# Motor-BLDC.net
KiCad netlist of a schematic drawn in Altium Designer
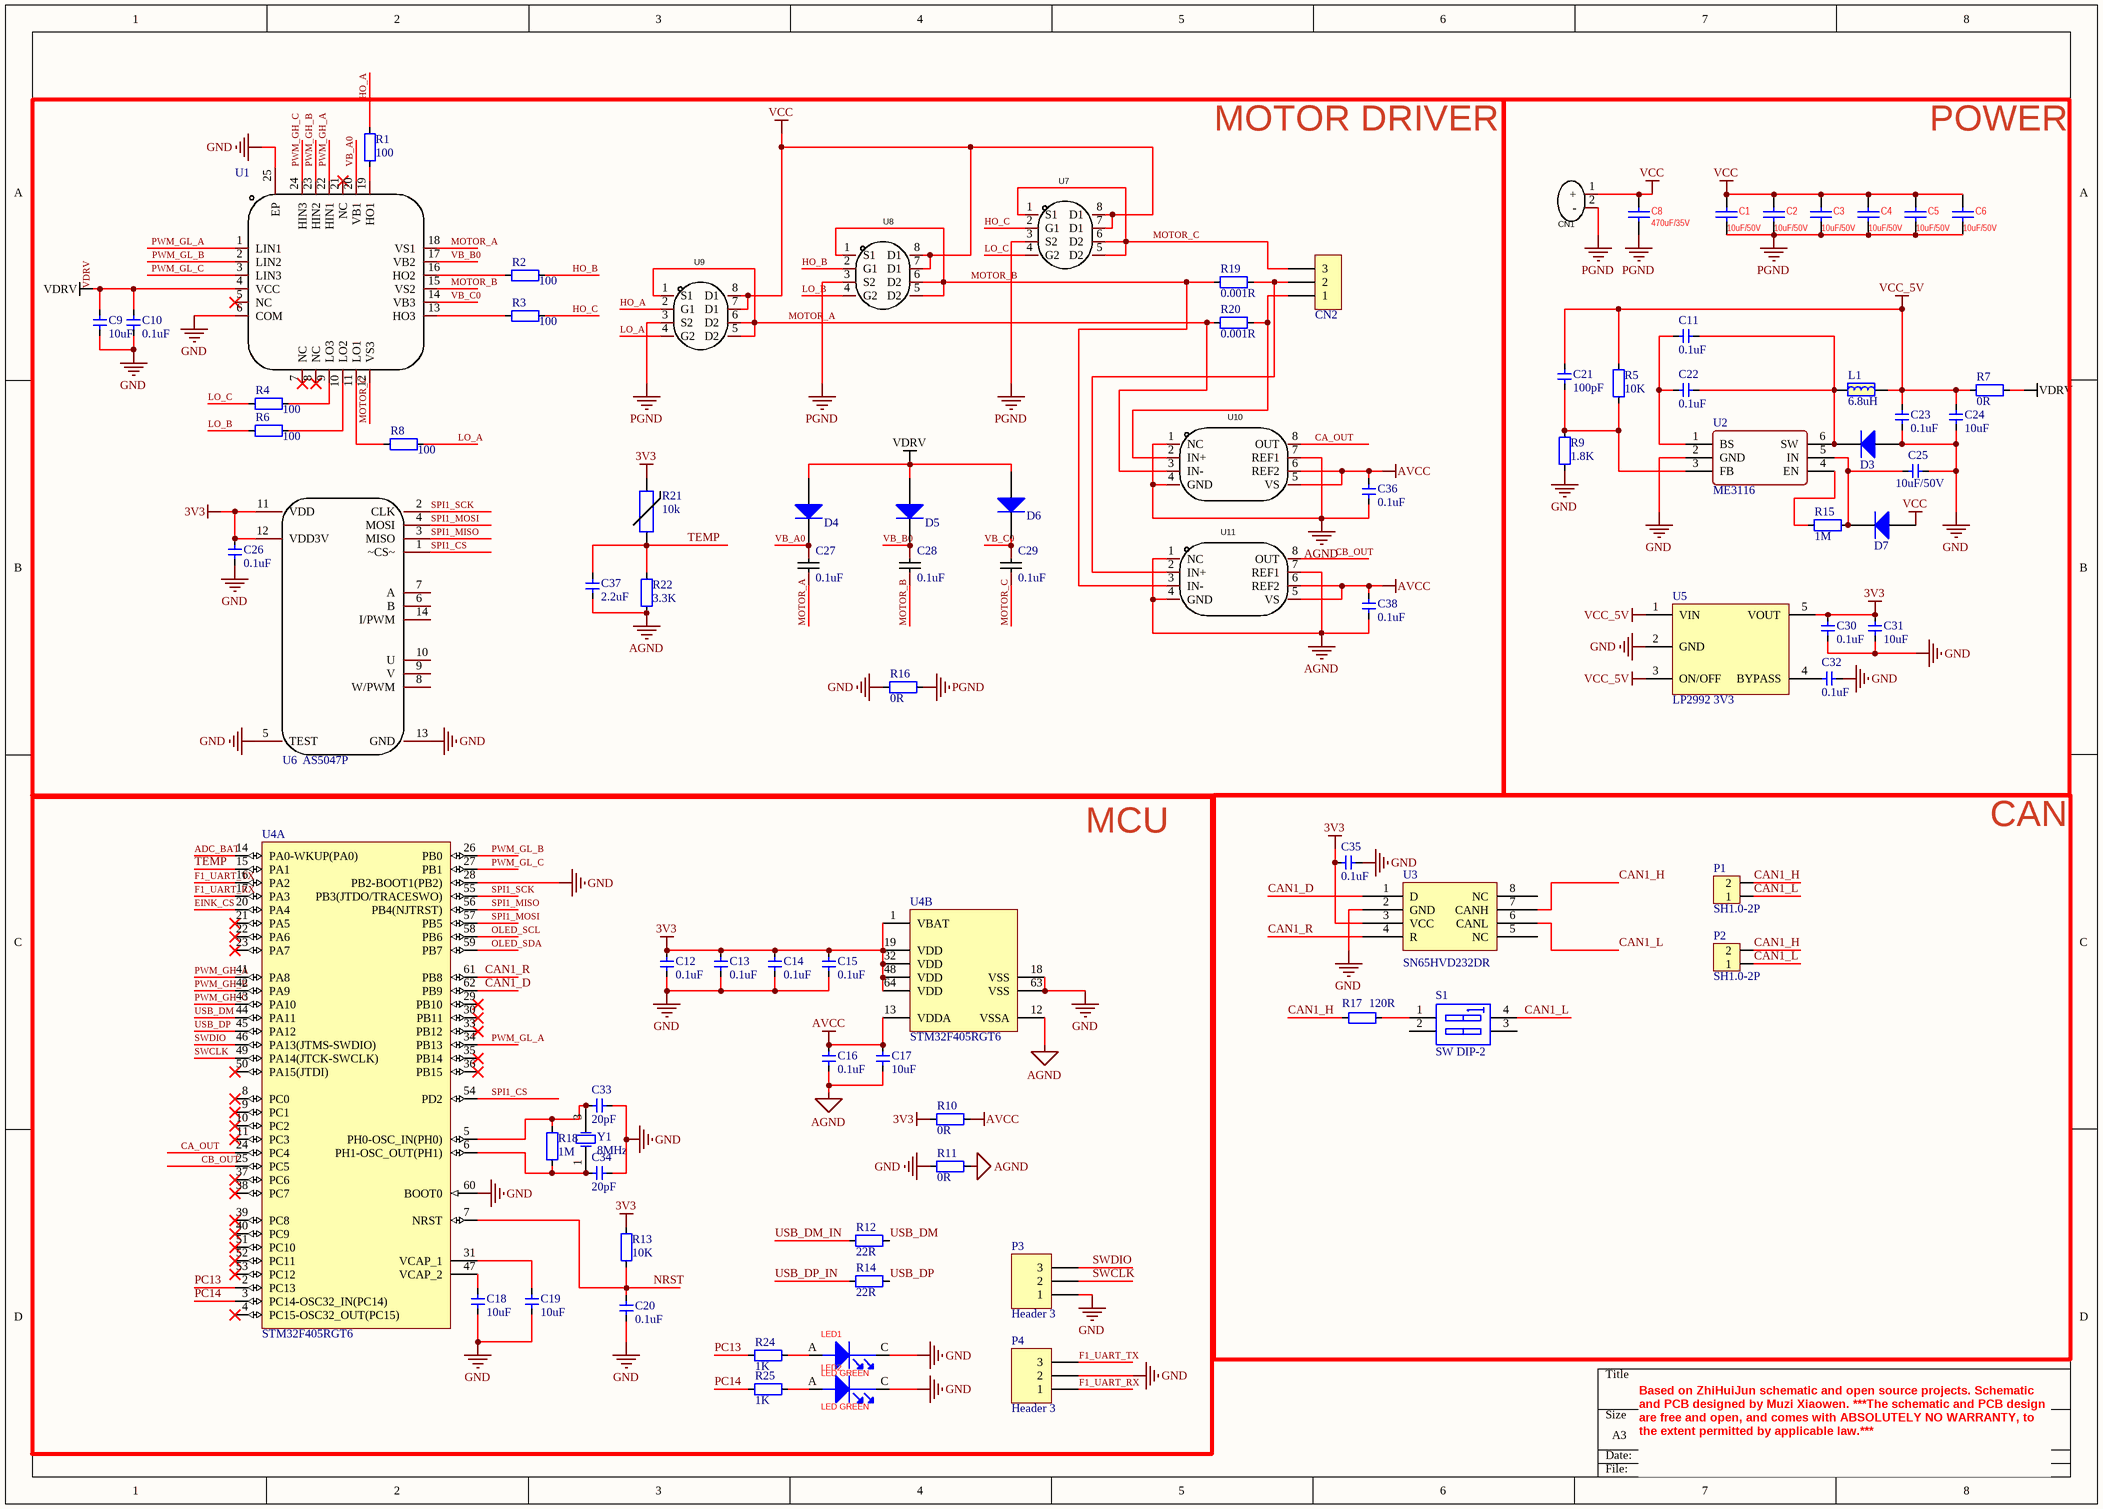
[diagram p0: Motor-BLDC.SchDoc]

(export (version "E")
  (design (tool "Eeschema 10.0.6"))
  (components
    (comp (ref "C1")
      (value "10uF/50V")
      (footprint "1206-CAP")
      (description "Capacitor, chip, ceramic")
      (libsource (lib "OAKUSBFXS") (part "CAP"))
    )
    (comp (ref "C2")
      (value "10uF/50V")
      (footprint "1206-CAP")
      (description "Capacitor, chip, ceramic")
      (libsource (lib "OAKUSBFXS") (part "CAP"))
    )
    (comp (ref "C3")
      (value "10uF/50V")
      (footprint "1206-CAP")
      (description "Capacitor, chip, ceramic")
      (libsource (lib "OAKUSBFXS") (part "CAP"))
    )
    (comp (ref "C4")
      (value "10uF/50V")
      (footprint "1206-CAP")
      (description "Capacitor, chip, ceramic")
      (libsource (lib "OAKUSBFXS") (part "CAP"))
    )
    (comp (ref "C5")
      (value "10uF/50V")
      (footprint "1206-CAP")
      (description "Capacitor, chip, ceramic")
      (libsource (lib "OAKUSBFXS") (part "CAP"))
    )
    (comp (ref "C6")
      (value "10uF/50V")
      (footprint "1206-CAP")
      (description "Capacitor, chip, ceramic")
      (libsource (lib "OAKUSBFXS") (part "CAP"))
    )
    (comp (ref "C8")
      (value "470uF/35V")
      (footprint "CAP-SMD_BD8.0-L8.3-W8.3-LS9.3")
      (description "Capacitor, chip, ceramic")
      (fields (field (name "Comment") "220uF/25V"))
      (libsource (lib "OAKUSBFXS") (part "CAP"))
    )
    (comp (ref "C9")
      (value "10uF")
      (footprint "CAP_0402")
      (description "Capacitor")
      (libsource (lib "Miscellaneous Connectors") (part "电容-0402"))
    )
    (comp (ref "C10")
      (value "0.1uF")
      (footprint "CAP_0402")
      (description "Capacitor")
      (libsource (lib "Miscellaneous Connectors") (part "电容-0402"))
    )
    (comp (ref "C11")
      (value "0.1uF")
      (footprint "CAP_0402")
      (description "Capacitor")
      (libsource (lib "Miscellaneous Connectors") (part "电容-0402"))
    )
    (comp (ref "C12")
      (value "0.1uF")
      (footprint "CAP_0402")
      (description "Capacitor")
      (libsource (lib "Miscellaneous Connectors") (part "电容-0402"))
    )
    (comp (ref "C13")
      (value "0.1uF")
      (footprint "CAP_0402")
      (description "Capacitor")
      (libsource (lib "Miscellaneous Connectors") (part "电容-0402"))
    )
    (comp (ref "C14")
      (value "0.1uF")
      (footprint "CAP_0402")
      (description "Capacitor")
      (libsource (lib "Miscellaneous Connectors") (part "电容-0402"))
    )
    (comp (ref "C15")
      (value "0.1uF")
      (footprint "CAP_0402")
      (description "Capacitor")
      (libsource (lib "Miscellaneous Connectors") (part "电容-0402"))
    )
    (comp (ref "C16")
      (value "0.1uF")
      (footprint "CAP_0402")
      (description "Capacitor")
      (libsource (lib "Miscellaneous Connectors") (part "电容-0402"))
    )
    (comp (ref "C17")
      (value "10uF")
      (footprint "CAP_0402")
      (description "Capacitor")
      (libsource (lib "Miscellaneous Connectors") (part "电容-0402"))
    )
    (comp (ref "C18")
      (value "10uF")
      (footprint "CAP_0402")
      (description "Capacitor")
      (libsource (lib "Miscellaneous Connectors") (part "电容-0402"))
    )
    (comp (ref "C19")
      (value "10uF")
      (footprint "CAP_0402")
      (description "Capacitor")
      (libsource (lib "Miscellaneous Connectors") (part "电容-0402"))
    )
    (comp (ref "C20")
      (value "0.1uF")
      (footprint "CAP_0402")
      (description "Capacitor")
      (libsource (lib "Miscellaneous Connectors") (part "电容-0402"))
    )
    (comp (ref "C21")
      (value "100pF")
      (footprint "CAP_0402")
      (description "Capacitor")
      (libsource (lib "Miscellaneous Connectors") (part "电容-0402"))
    )
    (comp (ref "C22")
      (value "0.1uF")
      (footprint "CAP_0402")
      (description "Capacitor")
      (libsource (lib "Miscellaneous Connectors") (part "电容-0402"))
    )
    (comp (ref "C23")
      (value "0.1uF")
      (footprint "CAP_0402")
      (description "Capacitor")
      (libsource (lib "Miscellaneous Connectors") (part "电容-0402"))
    )
    (comp (ref "C24")
      (value "10uF")
      (footprint "CAP_0402")
      (description "Capacitor")
      (libsource (lib "Miscellaneous Connectors") (part "电容-0402"))
    )
    (comp (ref "C25")
      (value "10uF/50V")
      (footprint "1206-CAP")
      (description "Capacitor")
      (libsource (lib "Miscellaneous Connectors") (part "电容-0402"))
    )
    (comp (ref "C26")
      (value "0.1uF")
      (footprint "CAP_0402")
      (description "Capacitor")
      (libsource (lib "Miscellaneous Connectors") (part "电容-0402"))
    )
    (comp (ref "C27")
      (value "0.1uF")
      (footprint "CAP_0402")
      (description "容值:10uF;精度:±20%;额定电压:6.3V;温度系数:X5R;")
      (fields
        (field (name "MANUFACTURER") "YAGEO(国巨)")
        (field (name "MANUFACTURER PART") "CC0402MRX5R5BB106")
      )
      (libsource (lib "altium-import") (part "root_1_CC0402MRX5R5BB106_"))
    )
    (comp (ref "C28")
      (value "0.1uF")
      (footprint "CAP_0402")
      (description "容值:10uF;精度:±20%;额定电压:6.3V;温度系数:X5R;")
      (fields
        (field (name "MANUFACTURER") "YAGEO(国巨)")
        (field (name "MANUFACTURER PART") "CC0402MRX5R5BB106")
      )
      (libsource (lib "altium-import") (part "root_1_CC0402MRX5R5BB106_"))
    )
    (comp (ref "C29")
      (value "0.1uF")
      (footprint "CAP_0402")
      (description "容值:10uF;精度:±20%;额定电压:6.3V;温度系数:X5R;")
      (fields
        (field (name "MANUFACTURER") "YAGEO(国巨)")
        (field (name "MANUFACTURER PART") "CC0402MRX5R5BB106")
      )
      (libsource (lib "altium-import") (part "root_1_CC0402MRX5R5BB106_"))
    )
    (comp (ref "C30")
      (value "0.1uF")
      (footprint "CAP_0402")
      (description "Capacitor")
      (libsource (lib "Miscellaneous Connectors") (part "电容-0402"))
    )
    (comp (ref "C31")
      (value "10uF")
      (footprint "CAP_0402")
      (description "Capacitor")
      (libsource (lib "Miscellaneous Connectors") (part "电容-0402"))
    )
    (comp (ref "C32")
      (value "0.1uF")
      (footprint "CAP_0402")
      (description "Capacitor")
      (libsource (lib "Miscellaneous Connectors") (part "电容-0402"))
    )
    (comp (ref "C33")
      (value "20pF")
      (footprint "CAP_0402")
      (description "Capacitor")
      (libsource (lib "Miscellaneous Connectors") (part "电容-0402"))
    )
    (comp (ref "C34")
      (value "20pF")
      (footprint "CAP_0402")
      (description "Capacitor")
      (libsource (lib "Miscellaneous Connectors") (part "电容-0402"))
    )
    (comp (ref "C35")
      (value "0.1uF")
      (footprint "CAP_0402")
      (description "Capacitor")
      (libsource (lib "Miscellaneous Connectors") (part "电容-0402"))
    )
    (comp (ref "C36")
      (value "0.1uF")
      (footprint "CAP_0402")
      (description "Capacitor")
      (libsource (lib "Miscellaneous Connectors") (part "电容-0402"))
    )
    (comp (ref "C37")
      (value "2.2uF")
      (footprint "CAP_0402")
      (description "Capacitor")
      (libsource (lib "MyPcbLib") (part "电容-0402"))
    )
    (comp (ref "C38")
      (value "0.1uF")
      (footprint "CAP_0402")
      (description "Capacitor")
      (libsource (lib "Miscellaneous Connectors") (part "电容-0402"))
    )
    (comp (ref "CN1")
      (value "XT30UPB-F30.G.Y")
      (footprint "CONN-TH_XT30UPB-F")
      (fields (field (name "MANUFACTURER") "AMASS(艾迈斯)"))
      (libsource (lib "altium-import") (part "root_0_mirrored_XT30UPB-F30.G.Y_"))
    )
    (comp (ref "CN2")
      (value "1704936")
      (footprint "MR30PW-M")
      (description "CONN TERM BLOCK 3POS 7.62MM")
      (fields (field (name "MANUFACTURER") "Phoenix Contact") (field (name "VOLTAGE") "300V"))
      (libsource (lib "CustomComponents") (part "1704936"))
    )
    (comp (ref "D3")
      (value "二极管-5819W")
      (footprint "SOD-323")
      (description "40V")
      (libsource (lib "Miscellaneous Connectors") (part "二极管-5819W"))
    )
    (comp (ref "D4")
      (value "二极管-5819W")
      (footprint "SOD-323")
      (description "40V")
      (libsource (lib "Miscellaneous Connectors") (part "二极管-5819W"))
    )
    (comp (ref "D5")
      (value "二极管-5819W")
      (footprint "SOD-323")
      (description "40V")
      (libsource (lib "Miscellaneous Connectors") (part "二极管-5819W"))
    )
    (comp (ref "D6")
      (value "二极管-5819W")
      (footprint "SOD-323")
      (description "40V")
      (libsource (lib "Miscellaneous Connectors") (part "二极管-5819W"))
    )
    (comp (ref "D7")
      (value "二极管-5819W")
      (footprint "SOD-323")
      (description "40V")
      (libsource (lib "Miscellaneous Connectors") (part "二极管-5819W"))
    )
    (comp (ref "L1")
      (value "6.8uH")
      (footprint "IND-201612")
      (libsource (lib "Miscellaneous Connectors") (part "电感-201612"))
    )
    (comp (ref "LED1")
      (value "LED GREEN")
      (footprint "LED-0603")
      (description "LED GRN SGL RA 25mA 4.1V SMD")
      (libsource (lib "*") (part "LED"))
    )
    (comp (ref "LED2")
      (value "LED GREEN")
      (footprint "LED-0603")
      (description "LED GRN SGL RA 25mA 4.1V SMD")
      (libsource (lib "*") (part "LED"))
    )
    (comp (ref "P1") (value "SH1.0-2P") (footprint "SH1.0-2P") (libsource (lib "MyPcbLib") (part "SH1.0-2P")))
    (comp (ref "P2") (value "SH1.0-2P") (footprint "SH1.0-2P") (libsource (lib "MyPcbLib") (part "SH1.0-2P")))
    (comp (ref "P3")
      (value "Header 3")
      (footprint "HDR1X3")
      (description "Header, 3-Pin")
      (fields (field (name "PUBLISHER") "Altium Limited"))
      (libsource (lib "Miscellaneous Connectors") (part "Header 3"))
    )
    (comp (ref "P4")
      (value "Header 3")
      (footprint "HDR1X3")
      (description "Header, 3-Pin")
      (fields (field (name "PUBLISHER") "Altium Limited"))
      (libsource (lib "Miscellaneous Connectors") (part "Header 3"))
    )
    (comp (ref "R1")
      (value "100")
      (footprint "RES_0402")
      (description "Resistor")
      (libsource (lib "Miscellaneous Connectors") (part "电阻-0402"))
    )
    (comp (ref "R2")
      (value "100")
      (footprint "RES_0402")
      (description "Resistor")
      (libsource (lib "") (part "电阻-0402_1"))
    )
    (comp (ref "R3")
      (value "100")
      (footprint "RES_0402")
      (description "Resistor")
      (libsource (lib "") (part "电阻-0402_1"))
    )
    (comp (ref "R4")
      (value "100")
      (footprint "RES_0402")
      (description "Resistor")
      (libsource (lib "") (part "电阻-0402_1"))
    )
    (comp (ref "R5")
      (value "10K")
      (footprint "RES_0402")
      (description "Resistor")
      (libsource (lib "") (part "电阻-0402_3"))
    )
    (comp (ref "R6")
      (value "100")
      (footprint "RES_0402")
      (description "Resistor")
      (libsource (lib "") (part "电阻-0402_1"))
    )
    (comp (ref "R7")
      (value "0R")
      (footprint "1206-RES")
      (description "Resistor")
      (libsource (lib "Miscellaneous Connectors") (part "电阻-1206"))
    )
    (comp (ref "R8")
      (value "100")
      (footprint "RES_0402")
      (description "Resistor")
      (libsource (lib "") (part "电阻-0402_1"))
    )
    (comp (ref "R9")
      (value "1.8K")
      (footprint "RES_0402")
      (description "Resistor")
      (libsource (lib "") (part "电阻-0402_3"))
    )
    (comp (ref "R10")
      (value "0R")
      (footprint "RES_0402")
      (description "Resistor")
      (libsource (lib "") (part "电阻-0402_1"))
    )
    (comp (ref "R11")
      (value "0R")
      (footprint "RES_0402")
      (description "Resistor")
      (libsource (lib "") (part "电阻-0402_1"))
    )
    (comp (ref "R12")
      (value "22R")
      (footprint "RES_0402")
      (description "Resistor")
      (libsource (lib "") (part "电阻-0402_1"))
    )
    (comp (ref "R13")
      (value "10K")
      (footprint "RES_0402")
      (description "Resistor")
      (libsource (lib "") (part "电阻-0402_3"))
    )
    (comp (ref "R14")
      (value "22R")
      (footprint "RES_0402")
      (description "Resistor")
      (libsource (lib "") (part "电阻-0402_1"))
    )
    (comp (ref "R15")
      (value "1M")
      (footprint "RES_0402")
      (description "Resistor")
      (libsource (lib "") (part "电阻-0402_1"))
    )
    (comp (ref "R16")
      (value "0R")
      (footprint "1206-RES")
      (description "Resistor")
      (libsource (lib "Miscellaneous Connectors") (part "电阻-1206"))
    )
    (comp (ref "R17")
      (value "120R")
      (footprint "RES_0402")
      (description "Resistor")
      (libsource (lib "") (part "电阻-0402_2"))
    )
    (comp (ref "R18")
      (value "1M")
      (footprint "RES_0402")
      (description "Resistor")
      (libsource (lib "Miscellaneous Connectors") (part "电阻-0402"))
    )
    (comp (ref "R19")
      (value "0.001R")
      (footprint "2512-RES")
      (description "Resistor")
      (libsource (lib "Miscellaneous Connectors") (part "电阻-1206"))
    )
    (comp (ref "R20")
      (value "0.001R")
      (footprint "2512-RES")
      (description "Resistor")
      (libsource (lib "Miscellaneous Connectors") (part "电阻-1206"))
    )
    (comp (ref "R21")
      (value "10k")
      (footprint "RES_0402")
      (description "THERMISTOR 10K OHM NTC 0402 SMD")
      (fields (field (name "Comment") "NCP15XH103F03RC"))
      (libsource (lib "MyPcbLib") (part "NCP15XH103F03RC"))
    )
    (comp (ref "R22")
      (value "3.3K")
      (footprint "RES_0402")
      (description "Resistor")
      (libsource (lib "MyPcbLib") (part "电阻-0402"))
    )
    (comp (ref "R24")
      (value "1K")
      (footprint "RES_0402")
      (description "Resistor")
      (libsource (lib "") (part "电阻-0402_1"))
    )
    (comp (ref "R25")
      (value "1K")
      (footprint "RES_0402")
      (description "Resistor")
      (libsource (lib "") (part "电阻-0402_1"))
    )
    (comp (ref "S1")
      (value "SW DIP-2")
      (footprint "SW-SMD_DSHP02")
      (description "DIP Switch, 2 Position, SPST")
      (fields (field (name "PUBLISHER") "Altium Limited"))
      (libsource (lib "Miscellaneous Devices") (part "SW DIP-2"))
    )
    (comp (ref "U1")
      (value "FD6288Q")
      (footprint "QFN-24_L4.0-W4.0-P0.50-BL")
      (fields (field (name "MANUFACTURER") "Fortior Tech(峰岹)"))
      (libsource (lib "altium-import") (part "root_0_FD6288Q_"))
    )
    (comp (ref "U2")
      (value "ME3116")
      (footprint "SOT23-6")
      (description "DC-DC")
      (libsource (lib "Miscellaneous Connectors") (part "ME3116"))
    )
    (comp (ref "U3")
      (value "SN65HVD232D")
      (footprint "SO-8")
      (fields
        (field (name "MANUFACTURER") "Texas Instruments")
        (field (name "MANUFACTURER PART NUMBER") "SN65HVD232DR")
      )
      (libsource (lib "Miscellaneous Connectors") (part "SN65HVD232D"))
    )
    (comp (ref "U4")
      (value "STM32F405RGT6")
      (footprint "LQFP-64_N")
      (fields (field (name "MANUFACTURER") "STMicroelectronics"))
      (libsource (lib "STMicroelectronics STM32 F4") (part "STM32F405RGT6"))
    )
    (comp (ref "U5")
      (value "LP2992 3V3")
      (footprint "SOT23-5")
      (description "LDO")
      (libsource (lib "Miscellaneous Connectors") (part "LP2992"))
    )
    (comp (ref "U6")
      (value "AS5047P")
      (footprint "TSSOP14")
      (fields (field (name "DEVICE") "AS5047P"))
      (libsource (lib "altium-import") (part "root_0_AS5047P_"))
    )
    (comp (ref "U7")
      (value "AP90N03GD")
      (footprint "DFN-8_L5.8-W4.9-P1.27-LS6.0")
      (fields (field (name "MANUFACTURER") "ALLPOWER(铨力)"))
      (libsource (lib "altium-import") (part "root_0_AP90N03GD_"))
    )
    (comp (ref "U8")
      (value "AP90N03GD")
      (footprint "DFN-8_L5.8-W4.9-P1.27-LS6.0")
      (fields (field (name "MANUFACTURER") "ALLPOWER(铨力)"))
      (libsource (lib "altium-import") (part "root_0_AP90N03GD_"))
    )
    (comp (ref "U9")
      (value "AP90N03GD")
      (footprint "DFN-8_L5.8-W4.9-P1.27-LS6.0")
      (fields (field (name "MANUFACTURER") "ALLPOWER(铨力)"))
      (libsource (lib "altium-import") (part "root_0_AP90N03GD_"))
    )
    (comp (ref "U10")
      (value "INA240A1PWR")
      (footprint "INA240")
      (fields (field (name "MANUFACTURER") "TI(德州仪器)"))
      (libsource (lib "altium-import") (part "root_0_INA240A1PWR_"))
    )
    (comp (ref "U11")
      (value "INA240A1PWR")
      (footprint "INA240")
      (fields (field (name "MANUFACTURER") "TI(德州仪器)"))
      (libsource (lib "altium-import") (part "root_0_INA240A1PWR_"))
    )
    (comp (ref "Y1")
      (value "8MHz")
      (footprint "LC-SMD-3225_4P")
      (description "Crystal")
      (fields (field (name "Comment") "XTAL-4"))
      (libsource (lib "rpi") (part "XTAL-4"))
    )
  )
  (nets
    (net (code "1") (name "/ADC_BAT") (class "Default")
      (node (ref "U4") (pin "14") (pinfunction "PA0-WKUP(PA0)_14") (pintype "bidirectional"))
    )
    (net (code "2") (name "/CAN1_D") (class "Default")
      (node (ref "U3") (pin "1") (pinfunction "D_1") (pintype "passive"))
      (node (ref "U4") (pin "62") (pinfunction "PB9_62") (pintype "bidirectional"))
    )
    (net (code "3") (name "/CAN1_H") (class "Default")
      (node (ref "P1") (pin "2") (pinfunction "2_2") (pintype "passive"))
      (node (ref "P2") (pin "2") (pinfunction "2_2") (pintype "passive"))
      (node (ref "R17") (pin "1") (pinfunction "1_1") (pintype "passive"))
      (node (ref "U3") (pin "7") (pinfunction "CANH_7") (pintype "passive"))
    )
    (net (code "4") (name "/CAN1_L") (class "Default")
      (node (ref "P1") (pin "1") (pinfunction "1_1") (pintype "passive"))
      (node (ref "P2") (pin "1") (pinfunction "1_1") (pintype "passive"))
      (node (ref "S1") (pin "4") (pinfunction "B1_4") (pintype "passive"))
      (node (ref "U3") (pin "6") (pinfunction "CANL_6") (pintype "passive"))
    )
    (net (code "5") (name "/CAN1_R") (class "Default")
      (node (ref "U3") (pin "4") (pinfunction "R_4") (pintype "passive"))
      (node (ref "U4") (pin "61") (pinfunction "PB8_61") (pintype "bidirectional"))
    )
    (net (code "6") (name "/CA_OUT") (class "Default")
      (node (ref "U10") (pin "8") (pinfunction "OUT_8") (pintype "passive"))
      (node (ref "U4") (pin "24") (pinfunction "PC4_24") (pintype "bidirectional"))
    )
    (net (code "7") (name "/CB_OUT") (class "Default")
      (node (ref "U11") (pin "8") (pinfunction "OUT_8") (pintype "passive"))
      (node (ref "U4") (pin "25") (pinfunction "PC5_25") (pintype "bidirectional"))
    )
    (net (code "8") (name "/EINK_CS") (class "Default")
      (node (ref "U4") (pin "20") (pinfunction "PA4_20") (pintype "bidirectional"))
    )
    (net (code "9") (name "/F1_UART_RX") (class "Default")
      (node (ref "P4") (pin "1") (pinfunction "1_1") (pintype "passive"))
      (node (ref "U4") (pin "17") (pinfunction "PA3_17") (pintype "bidirectional"))
    )
    (net (code "10") (name "/F1_UART_TX") (class "Default")
      (node (ref "P4") (pin "3") (pinfunction "3_3") (pintype "passive"))
      (node (ref "U4") (pin "16") (pinfunction "PA2_16") (pintype "bidirectional"))
    )
    (net (code "11") (name "/HO_A") (class "Default")
      (node (ref "R1") (pin "1") (pinfunction "1_1") (pintype "passive"))
      (node (ref "U9") (pin "2") (pinfunction "G1_2") (pintype "passive"))
    )
    (net (code "12") (name "/HO_B") (class "Default")
      (node (ref "R2") (pin "1") (pinfunction "1_1") (pintype "passive"))
      (node (ref "U8") (pin "2") (pinfunction "G1_2") (pintype "passive"))
    )
    (net (code "13") (name "/HO_C") (class "Default")
      (node (ref "R3") (pin "1") (pinfunction "1_1") (pintype "passive"))
      (node (ref "U7") (pin "2") (pinfunction "G1_2") (pintype "passive"))
    )
    (net (code "14") (name "/LO_A") (class "Default")
      (node (ref "R8") (pin "1") (pinfunction "1_1") (pintype "passive"))
      (node (ref "U9") (pin "4") (pinfunction "G2_4") (pintype "passive"))
    )
    (net (code "15") (name "/LO_B") (class "Default")
      (node (ref "R6") (pin "2") (pinfunction "2_2") (pintype "passive"))
      (node (ref "U8") (pin "4") (pinfunction "G2_4") (pintype "passive"))
    )
    (net (code "16") (name "/LO_C") (class "Default")
      (node (ref "R4") (pin "2") (pinfunction "2_2") (pintype "passive"))
      (node (ref "U7") (pin "4") (pinfunction "G2_4") (pintype "passive"))
    )
    (net (code "17") (name "/MOTOR_A") (class "Default")
      (node (ref "C27") (pin "1") (pinfunction "1_1") (pintype "passive"))
      (node (ref "R20") (pin "1") (pinfunction "1_1") (pintype "passive"))
      (node (ref "U1") (pin "18") (pinfunction "VS1_18") (pintype "passive"))
      (node (ref "U10") (pin "3") (pinfunction "IN-_3") (pintype "passive"))
      (node (ref "U9") (pin "1") (pinfunction "S1_1") (pintype "passive"))
      (node (ref "U9") (pin "5") (pinfunction "D2_5") (pintype "passive"))
      (node (ref "U9") (pin "6") (pinfunction "D2_6") (pintype "passive"))
    )
    (net (code "18") (name "/MOTOR_B") (class "Default")
      (node (ref "C28") (pin "1") (pinfunction "1_1") (pintype "passive"))
      (node (ref "R19") (pin "1") (pinfunction "1_1") (pintype "passive"))
      (node (ref "U1") (pin "15") (pinfunction "VS2_15") (pintype "passive"))
      (node (ref "U11") (pin "3") (pinfunction "IN-_3") (pintype "passive"))
      (node (ref "U8") (pin "1") (pinfunction "S1_1") (pintype "passive"))
      (node (ref "U8") (pin "5") (pinfunction "D2_5") (pintype "passive"))
      (node (ref "U8") (pin "6") (pinfunction "D2_6") (pintype "passive"))
    )
    (net (code "19") (name "/MOTOR_C") (class "Default")
      (node (ref "C29") (pin "1") (pinfunction "1_1") (pintype "passive"))
      (node (ref "CN2") (pin "3") (pinfunction "3_3") (pintype "passive"))
      (node (ref "U1") (pin "12") (pinfunction "VS3_12") (pintype "passive"))
      (node (ref "U7") (pin "1") (pinfunction "S1_1") (pintype "passive"))
      (node (ref "U7") (pin "5") (pinfunction "D2_5") (pintype "passive"))
      (node (ref "U7") (pin "6") (pinfunction "D2_6") (pintype "passive"))
    )
    (net (code "20") (name "/NRST") (class "Default")
      (node (ref "C20") (pin "2") (pinfunction "2_2") (pintype "passive"))
      (node (ref "R13") (pin "1") (pinfunction "1_1") (pintype "passive"))
      (node (ref "U4") (pin "7") (pinfunction "NRST_7") (pintype "bidirectional"))
    )
    (net (code "21") (name "/OLED_SCL") (class "Default")
      (node (ref "U4") (pin "58") (pinfunction "PB6_58") (pintype "bidirectional"))
    )
    (net (code "22") (name "/OLED_SDA") (class "Default")
      (node (ref "U4") (pin "59") (pinfunction "PB7_59") (pintype "bidirectional"))
    )
    (net (code "23") (name "/PC13") (class "Default")
      (node (ref "R24") (pin "1") (pinfunction "1_1") (pintype "passive"))
      (node (ref "U4") (pin "2") (pinfunction "PC13_2") (pintype "bidirectional"))
    )
    (net (code "24") (name "/PC14") (class "Default")
      (node (ref "R25") (pin "1") (pinfunction "1_1") (pintype "passive"))
      (node (ref "U4") (pin "3") (pinfunction "PC14-OSC32_IN(PC14)_3") (pintype "bidirectional"))
    )
    (net (code "25") (name "/PWM_GH_A") (class "Default")
      (node (ref "U1") (pin "22") (pinfunction "HIN1_22") (pintype "passive"))
      (node (ref "U4") (pin "41") (pinfunction "PA8_41") (pintype "bidirectional"))
    )
    (net (code "26") (name "/PWM_GH_B") (class "Default")
      (node (ref "U1") (pin "23") (pinfunction "HIN2_23") (pintype "passive"))
      (node (ref "U4") (pin "42") (pinfunction "PA9_42") (pintype "bidirectional"))
    )
    (net (code "27") (name "/PWM_GH_C") (class "Default")
      (node (ref "U1") (pin "24") (pinfunction "HIN3_24") (pintype "passive"))
      (node (ref "U4") (pin "43") (pinfunction "PA10_43") (pintype "bidirectional"))
    )
    (net (code "28") (name "/PWM_GL_A") (class "Default")
      (node (ref "U1") (pin "1") (pinfunction "LIN1_1") (pintype "passive"))
      (node (ref "U4") (pin "34") (pinfunction "PB13_34") (pintype "bidirectional"))
    )
    (net (code "29") (name "/PWM_GL_B") (class "Default")
      (node (ref "U1") (pin "2") (pinfunction "LIN2_2") (pintype "passive"))
      (node (ref "U4") (pin "26") (pinfunction "PB0_26") (pintype "bidirectional"))
    )
    (net (code "30") (name "/PWM_GL_C") (class "Default")
      (node (ref "U1") (pin "3") (pinfunction "LIN3_3") (pintype "passive"))
      (node (ref "U4") (pin "27") (pinfunction "PB1_27") (pintype "bidirectional"))
    )
    (net (code "31") (name "/SPI1_CS") (class "Default")
      (node (ref "U4") (pin "54") (pinfunction "PD2_54") (pintype "bidirectional"))
      (node (ref "U6") (pin "1") (pinfunction "~CS~_1") (pintype "passive"))
    )
    (net (code "32") (name "/SPI1_MISO") (class "Default")
      (node (ref "U4") (pin "56") (pinfunction "PB4(NJTRST)_56") (pintype "bidirectional"))
      (node (ref "U6") (pin "3") (pinfunction "MISO_3") (pintype "passive"))
    )
    (net (code "33") (name "/SPI1_MOSI") (class "Default")
      (node (ref "U4") (pin "57") (pinfunction "PB5_57") (pintype "bidirectional"))
      (node (ref "U6") (pin "4") (pinfunction "MOSI_4") (pintype "passive"))
    )
    (net (code "34") (name "/SPI1_SCK") (class "Default")
      (node (ref "U4") (pin "55") (pinfunction "PB3(JTDO/TRACESWO)_55") (pintype "bidirectional"))
      (node (ref "U6") (pin "2") (pinfunction "CLK_2") (pintype "passive"))
    )
    (net (code "35") (name "/SWCLK") (class "Default")
      (node (ref "P3") (pin "2") (pinfunction "2_2") (pintype "passive"))
      (node (ref "U4") (pin "49") (pinfunction "PA14(JTCK-SWCLK)_49") (pintype "bidirectional"))
    )
    (net (code "36") (name "/SWDIO") (class "Default")
      (node (ref "P3") (pin "3") (pinfunction "3_3") (pintype "passive"))
      (node (ref "U4") (pin "46") (pinfunction "PA13(JTMS-SWDIO)_46") (pintype "bidirectional"))
    )
    (net (code "37") (name "/TEMP") (class "Default")
      (node (ref "C37") (pin "2") (pinfunction "2_2") (pintype "passive"))
      (node (ref "R21") (pin "1") (pinfunction "0_1") (pintype "passive"))
      (node (ref "R22") (pin "2") (pinfunction "2_2") (pintype "passive"))
      (node (ref "U4") (pin "15") (pinfunction "PA1_15") (pintype "bidirectional"))
    )
    (net (code "38") (name "/USB_DM") (class "Default")
      (node (ref "R12") (pin "1") (pinfunction "1_1") (pintype "passive"))
      (node (ref "U4") (pin "44") (pinfunction "PA11_44") (pintype "bidirectional"))
    )
    (net (code "39") (name "/USB_DM_IN") (class "Default")
      (node (ref "R12") (pin "2") (pinfunction "2_2") (pintype "passive"))
    )
    (net (code "40") (name "/USB_DP") (class "Default")
      (node (ref "R14") (pin "1") (pinfunction "1_1") (pintype "passive"))
      (node (ref "U4") (pin "45") (pinfunction "PA12_45") (pintype "bidirectional"))
    )
    (net (code "41") (name "/USB_DP_IN") (class "Default")
      (node (ref "R14") (pin "2") (pinfunction "2_2") (pintype "passive"))
    )
    (net (code "42") (name "/VB_A0") (class "Default")
      (node (ref "C27") (pin "2") (pinfunction "2_2") (pintype "passive"))
      (node (ref "D4") (pin "2") (pinfunction "K_2") (pintype "passive"))
      (node (ref "U1") (pin "20") (pinfunction "VB1_20") (pintype "passive"))
    )
    (net (code "43") (name "/VB_B0") (class "Default")
      (node (ref "C28") (pin "2") (pinfunction "2_2") (pintype "passive"))
      (node (ref "D5") (pin "2") (pinfunction "K_2") (pintype "passive"))
      (node (ref "U1") (pin "17") (pinfunction "VB2_17") (pintype "passive"))
    )
    (net (code "44") (name "/VB_C0") (class "Default")
      (node (ref "C29") (pin "2") (pinfunction "2_2") (pintype "passive"))
      (node (ref "D6") (pin "2") (pinfunction "K_2") (pintype "passive"))
      (node (ref "U1") (pin "14") (pinfunction "VB3_14") (pintype "passive"))
    )
    (net (code "45") (name "3V3") (class "Default")
      (node (ref "C12") (pin "2") (pinfunction "2_2") (pintype "passive"))
      (node (ref "C13") (pin "2") (pinfunction "2_2") (pintype "passive"))
      (node (ref "C14") (pin "2") (pinfunction "2_2") (pintype "passive"))
      (node (ref "C15") (pin "2") (pinfunction "2_2") (pintype "passive"))
      (node (ref "C26") (pin "2") (pinfunction "2_2") (pintype "passive"))
      (node (ref "C30") (pin "2") (pinfunction "2_2") (pintype "passive"))
      (node (ref "C31") (pin "2") (pinfunction "2_2") (pintype "passive"))
      (node (ref "C35") (pin "2") (pinfunction "2_2") (pintype "passive"))
      (node (ref "R10") (pin "2") (pinfunction "2_2") (pintype "passive"))
      (node (ref "R13") (pin "2") (pinfunction "2_2") (pintype "passive"))
      (node (ref "R21") (pin "2") (pinfunction "0_2") (pintype "passive"))
      (node (ref "U3") (pin "3") (pinfunction "VCC_3") (pintype "passive"))
      (node (ref "U4") (pin "1") (pinfunction "VBAT_1") (pintype "power_in"))
      (node (ref "U4") (pin "19") (pinfunction "VDD_19") (pintype "power_in"))
      (node (ref "U4") (pin "32") (pinfunction "VDD_32") (pintype "power_in"))
      (node (ref "U4") (pin "48") (pinfunction "VDD_48") (pintype "power_in"))
      (node (ref "U4") (pin "64") (pinfunction "VDD_64") (pintype "power_in"))
      (node (ref "U5") (pin "5") (pinfunction "VOUT_5") (pintype "passive"))
      (node (ref "U6") (pin "11") (pinfunction "VDD_11") (pintype "passive"))
      (node (ref "U6") (pin "12") (pinfunction "VDD3V_12") (pintype "passive"))
    )
    (net (code "46") (name "AGND") (class "Default")
      (node (ref "C16") (pin "1") (pinfunction "1_1") (pintype "passive"))
      (node (ref "C17") (pin "1") (pinfunction "1_1") (pintype "passive"))
      (node (ref "C36") (pin "1") (pinfunction "1_1") (pintype "passive"))
      (node (ref "C37") (pin "1") (pinfunction "1_1") (pintype "passive"))
      (node (ref "C38") (pin "1") (pinfunction "1_1") (pintype "passive"))
      (node (ref "R11") (pin "1") (pinfunction "1_1") (pintype "passive"))
      (node (ref "R22") (pin "1") (pinfunction "1_1") (pintype "passive"))
      (node (ref "U10") (pin "1") (pinfunction "NC_1") (pintype "passive"))
      (node (ref "U10") (pin "4") (pinfunction "GND_4") (pintype "passive"))
      (node (ref "U10") (pin "7") (pinfunction "REF1_7") (pintype "passive"))
      (node (ref "U11") (pin "1") (pinfunction "NC_1") (pintype "passive"))
      (node (ref "U11") (pin "4") (pinfunction "GND_4") (pintype "passive"))
      (node (ref "U11") (pin "7") (pinfunction "REF1_7") (pintype "passive"))
      (node (ref "U4") (pin "12") (pinfunction "VSSA_12") (pintype "power_in"))
    )
    (net (code "47") (name "AVCC") (class "Default")
      (node (ref "C16") (pin "2") (pinfunction "2_2") (pintype "passive"))
      (node (ref "C17") (pin "2") (pinfunction "2_2") (pintype "passive"))
      (node (ref "C36") (pin "2") (pinfunction "2_2") (pintype "passive"))
      (node (ref "C38") (pin "2") (pinfunction "2_2") (pintype "passive"))
      (node (ref "R10") (pin "1") (pinfunction "1_1") (pintype "passive"))
      (node (ref "U10") (pin "5") (pinfunction "VS_5") (pintype "passive"))
      (node (ref "U10") (pin "6") (pinfunction "REF2_6") (pintype "passive"))
      (node (ref "U11") (pin "5") (pinfunction "VS_5") (pintype "passive"))
      (node (ref "U11") (pin "6") (pinfunction "REF2_6") (pintype "passive"))
      (node (ref "U4") (pin "13") (pinfunction "VDDA_13") (pintype "power_in"))
    )
    (net (code "48") (name "GND") (class "Default")
      (node (ref "C10") (pin "1") (pinfunction "1_1") (pintype "passive"))
      (node (ref "C12") (pin "1") (pinfunction "1_1") (pintype "passive"))
      (node (ref "C13") (pin "1") (pinfunction "1_1") (pintype "passive"))
      (node (ref "C14") (pin "1") (pinfunction "1_1") (pintype "passive"))
      (node (ref "C15") (pin "1") (pinfunction "1_1") (pintype "passive"))
      (node (ref "C18") (pin "1") (pinfunction "1_1") (pintype "passive"))
      (node (ref "C19") (pin "1") (pinfunction "1_1") (pintype "passive"))
      (node (ref "C20") (pin "1") (pinfunction "1_1") (pintype "passive"))
      (node (ref "C23") (pin "1") (pinfunction "1_1") (pintype "passive"))
      (node (ref "C24") (pin "1") (pinfunction "1_1") (pintype "passive"))
      (node (ref "C25") (pin "1") (pinfunction "1_1") (pintype "passive"))
      (node (ref "C26") (pin "1") (pinfunction "1_1") (pintype "passive"))
      (node (ref "C30") (pin "1") (pinfunction "1_1") (pintype "passive"))
      (node (ref "C31") (pin "1") (pinfunction "1_1") (pintype "passive"))
      (node (ref "C32") (pin "1") (pinfunction "1_1") (pintype "passive"))
      (node (ref "C33") (pin "2") (pinfunction "2_2") (pintype "passive"))
      (node (ref "C34") (pin "2") (pinfunction "2_2") (pintype "passive"))
      (node (ref "C35") (pin "1") (pinfunction "1_1") (pintype "passive"))
      (node (ref "C9") (pin "1") (pinfunction "1_1") (pintype "passive"))
      (node (ref "D3") (pin "1") (pinfunction "A_1") (pintype "passive"))
      (node (ref "LED1") (pin "C") (pinfunction "CATHODE_C") (pintype "passive"))
      (node (ref "LED2") (pin "C") (pinfunction "CATHODE_C") (pintype "passive"))
      (node (ref "P3") (pin "1") (pinfunction "1_1") (pintype "passive"))
      (node (ref "P4") (pin "2") (pinfunction "2_2") (pintype "passive"))
      (node (ref "R11") (pin "2") (pinfunction "2_2") (pintype "passive"))
      (node (ref "R16") (pin "1") (pinfunction "1_1") (pintype "passive"))
      (node (ref "R9") (pin "1") (pinfunction "1_1") (pintype "passive"))
      (node (ref "U1") (pin "25") (pinfunction "EP_25") (pintype "passive"))
      (node (ref "U1") (pin "6") (pinfunction "COM_6") (pintype "passive"))
      (node (ref "U2") (pin "2") (pinfunction "GND_2") (pintype "passive"))
      (node (ref "U3") (pin "2") (pinfunction "GND_2") (pintype "passive"))
      (node (ref "U4") (pin "18") (pinfunction "VSS_18") (pintype "power_in"))
      (node (ref "U4") (pin "28") (pinfunction "PB2-BOOT1(PB2)_28") (pintype "bidirectional"))
      (node (ref "U4") (pin "60") (pinfunction "BOOT0_60") (pintype "input"))
      (node (ref "U4") (pin "63") (pinfunction "VSS_63") (pintype "power_in"))
      (node (ref "U5") (pin "2") (pinfunction "GND_2") (pintype "passive"))
      (node (ref "U6") (pin "13") (pinfunction "GND_13") (pintype "passive"))
      (node (ref "U6") (pin "5") (pinfunction "TEST_5") (pintype "passive"))
    )
    (net (code "49") (name "Net-(D3-K)") (class "Default")
      (node (ref "C11") (pin "1") (pinfunction "1_1") (pintype "passive"))
      (node (ref "C22") (pin "1") (pinfunction "1_1") (pintype "passive"))
      (node (ref "D3") (pin "2") (pinfunction "K_2") (pintype "passive"))
      (node (ref "L1") (pin "1") (pintype "passive"))
      (node (ref "U2") (pin "6") (pinfunction "SW_6") (pintype "passive"))
    )
    (net (code "50") (name "Net-(D7-K)") (class "Default")
      (node (ref "C25") (pin "2") (pinfunction "2_2") (pintype "passive"))
      (node (ref "D7") (pin "2") (pinfunction "K_2") (pintype "passive"))
      (node (ref "R15") (pin "1") (pinfunction "1_1") (pintype "passive"))
      (node (ref "U2") (pin "5") (pinfunction "IN_5") (pintype "passive"))
    )
    (net (code "51") (name "Net-(LED1-ANODE)") (class "Default")
      (node (ref "LED1") (pin "A") (pinfunction "ANODE_A") (pintype "passive"))
      (node (ref "R24") (pin "2") (pinfunction "2_2") (pintype "passive"))
    )
    (net (code "52") (name "Net-(LED2-ANODE)") (class "Default")
      (node (ref "LED2") (pin "A") (pinfunction "ANODE_A") (pintype "passive"))
      (node (ref "R25") (pin "2") (pinfunction "2_2") (pintype "passive"))
    )
    (net (code "53") (name "Net-(S1-A1)") (class "Default")
      (node (ref "R17") (pin "2") (pinfunction "2_2") (pintype "passive"))
      (node (ref "S1") (pin "1") (pinfunction "A1_1") (pintype "passive"))
    )
    (net (code "54") (name "Net-(U1-HO1)") (class "Default")
      (node (ref "R1") (pin "2") (pinfunction "2_2") (pintype "passive"))
      (node (ref "U1") (pin "19") (pinfunction "HO1_19") (pintype "passive"))
    )
    (net (code "55") (name "Net-(U1-HO2)") (class "Default")
      (node (ref "R2") (pin "2") (pinfunction "2_2") (pintype "passive"))
      (node (ref "U1") (pin "16") (pinfunction "HO2_16") (pintype "passive"))
    )
    (net (code "56") (name "Net-(U1-HO3)") (class "Default")
      (node (ref "R3") (pin "2") (pinfunction "2_2") (pintype "passive"))
      (node (ref "U1") (pin "13") (pinfunction "HO3_13") (pintype "passive"))
    )
    (net (code "57") (name "Net-(U1-LO1)") (class "Default")
      (node (ref "R8") (pin "2") (pinfunction "2_2") (pintype "passive"))
      (node (ref "U1") (pin "11") (pinfunction "LO1_11") (pintype "passive"))
    )
    (net (code "58") (name "Net-(U1-LO2)") (class "Default")
      (node (ref "R6") (pin "1") (pinfunction "1_1") (pintype "passive"))
      (node (ref "U1") (pin "10") (pinfunction "LO2_10") (pintype "passive"))
    )
    (net (code "59") (name "Net-(U1-LO3)") (class "Default")
      (node (ref "R4") (pin "1") (pinfunction "1_1") (pintype "passive"))
      (node (ref "U1") (pin "9") (pinfunction "LO3_9") (pintype "passive"))
    )
    (net (code "60") (name "Net-(U2-BS)") (class "Default")
      (node (ref "C11") (pin "2") (pinfunction "2_2") (pintype "passive"))
      (node (ref "C22") (pin "2") (pinfunction "2_2") (pintype "passive"))
      (node (ref "U2") (pin "1") (pinfunction "BS_1") (pintype "passive"))
    )
    (net (code "61") (name "Net-(U2-EN)") (class "Default")
      (node (ref "R15") (pin "2") (pinfunction "2_2") (pintype "passive"))
      (node (ref "U2") (pin "4") (pinfunction "EN_4") (pintype "passive"))
    )
    (net (code "62") (name "Net-(U2-FB)") (class "Default")
      (node (ref "C21") (pin "2") (pinfunction "2_2") (pintype "passive"))
      (node (ref "R5") (pin "1") (pinfunction "1_1") (pintype "passive"))
      (node (ref "R9") (pin "2") (pinfunction "2_2") (pintype "passive"))
      (node (ref "U2") (pin "3") (pinfunction "FB_3") (pintype "passive"))
    )
    (net (code "63") (name "Net-(U4A-PH0-OSC_IN(PH0))") (class "Default")
      (node (ref "C33") (pin "1") (pinfunction "1_1") (pintype "passive"))
      (node (ref "R18") (pin "1") (pinfunction "1_1") (pintype "passive"))
      (node (ref "U4") (pin "5") (pinfunction "PH0-OSC_IN(PH0)_5") (pintype "bidirectional"))
      (node (ref "Y1") (pin "3") (pinfunction "OSC2_3") (pintype "passive"))
    )
    (net (code "64") (name "Net-(U4A-PH1-OSC_OUT(PH1))") (class "Default")
      (node (ref "C34") (pin "1") (pinfunction "1_1") (pintype "passive"))
      (node (ref "R18") (pin "2") (pinfunction "2_2") (pintype "passive"))
      (node (ref "U4") (pin "6") (pinfunction "PH1-OSC_OUT(PH1)_6") (pintype "bidirectional"))
      (node (ref "Y1") (pin "1") (pinfunction "OSC1_1") (pintype "passive"))
    )
    (net (code "65") (name "Net-(U4A-VCAP_1)") (class "Default")
      (node (ref "C19") (pin "2") (pinfunction "2_2") (pintype "passive"))
      (node (ref "U4") (pin "31") (pinfunction "VCAP_1_31") (pintype "power_in"))
    )
    (net (code "66") (name "Net-(U4A-VCAP_2)") (class "Default")
      (node (ref "C18") (pin "2") (pinfunction "2_2") (pintype "passive"))
      (node (ref "U4") (pin "47") (pinfunction "VCAP_2_47") (pintype "power_in"))
    )
    (net (code "67") (name "Net-(U5-BYPASS)") (class "Default")
      (node (ref "C32") (pin "2") (pinfunction "2_2") (pintype "passive"))
      (node (ref "U5") (pin "4") (pinfunction "BYPASS_4") (pintype "passive"))
    )
    (net (code "68") (name "Net-(U10-IN+)") (class "Default")
      (node (ref "CN2") (pin "1") (pinfunction "1_1") (pintype "passive"))
      (node (ref "R20") (pin "2") (pinfunction "2_2") (pintype "passive"))
      (node (ref "U10") (pin "2") (pinfunction "IN+_2") (pintype "passive"))
    )
    (net (code "69") (name "Net-(U11-IN+)") (class "Default")
      (node (ref "CN2") (pin "2") (pinfunction "2_2") (pintype "passive"))
      (node (ref "R19") (pin "2") (pinfunction "2_2") (pintype "passive"))
      (node (ref "U11") (pin "2") (pinfunction "IN+_2") (pintype "passive"))
    )
    (net (code "70") (name "PGND") (class "Default")
      (node (ref "C1") (pin "2") (pinfunction "2_2") (pintype "passive"))
      (node (ref "C2") (pin "2") (pinfunction "2_2") (pintype "passive"))
      (node (ref "C3") (pin "2") (pinfunction "2_2") (pintype "passive"))
      (node (ref "C4") (pin "2") (pinfunction "2_2") (pintype "passive"))
      (node (ref "C5") (pin "2") (pinfunction "2_2") (pintype "passive"))
      (node (ref "C6") (pin "2") (pinfunction "2_2") (pintype "passive"))
      (node (ref "C8") (pin "2") (pinfunction "2_2") (pintype "passive"))
      (node (ref "CN1") (pin "2") (pinfunction "-_2") (pintype "passive"))
      (node (ref "R16") (pin "2") (pinfunction "2_2") (pintype "passive"))
      (node (ref "U7") (pin "3") (pinfunction "S2_3") (pintype "passive"))
      (node (ref "U8") (pin "3") (pinfunction "S2_3") (pintype "passive"))
      (node (ref "U9") (pin "3") (pinfunction "S2_3") (pintype "passive"))
    )
    (net (code "71") (name "VCC") (class "Default")
      (node (ref "C1") (pin "1") (pinfunction "1_1") (pintype "passive"))
      (node (ref "C2") (pin "1") (pinfunction "1_1") (pintype "passive"))
      (node (ref "C3") (pin "1") (pinfunction "1_1") (pintype "passive"))
      (node (ref "C4") (pin "1") (pinfunction "1_1") (pintype "passive"))
      (node (ref "C5") (pin "1") (pinfunction "1_1") (pintype "passive"))
      (node (ref "C6") (pin "1") (pinfunction "1_1") (pintype "passive"))
      (node (ref "C8") (pin "1") (pinfunction "1_1") (pintype "passive"))
      (node (ref "CN1") (pin "1") (pinfunction "+_1") (pintype "passive"))
      (node (ref "D7") (pin "1") (pinfunction "A_1") (pintype "passive"))
      (node (ref "U7") (pin "7") (pinfunction "D1_7") (pintype "passive"))
      (node (ref "U7") (pin "8") (pinfunction "D1_8") (pintype "passive"))
      (node (ref "U8") (pin "7") (pinfunction "D1_7") (pintype "passive"))
      (node (ref "U8") (pin "8") (pinfunction "D1_8") (pintype "passive"))
      (node (ref "U9") (pin "7") (pinfunction "D1_7") (pintype "passive"))
      (node (ref "U9") (pin "8") (pinfunction "D1_8") (pintype "passive"))
    )
    (net (code "72") (name "VCC_5V") (class "Default")
      (node (ref "C21") (pin "1") (pinfunction "1_1") (pintype "passive"))
      (node (ref "C23") (pin "2") (pinfunction "2_2") (pintype "passive"))
      (node (ref "C24") (pin "2") (pinfunction "2_2") (pintype "passive"))
      (node (ref "L1") (pin "2") (pinfunction "2_2") (pintype "passive"))
      (node (ref "R5") (pin "2") (pinfunction "2_2") (pintype "passive"))
      (node (ref "R7") (pin "1") (pinfunction "1_1") (pintype "passive"))
      (node (ref "U5") (pin "1") (pinfunction "VIN_1") (pintype "passive"))
      (node (ref "U5") (pin "3") (pinfunction "ON/OFF_3") (pintype "passive"))
    )
    (net (code "73") (name "VDRV") (class "Default")
      (node (ref "C10") (pin "2") (pinfunction "2_2") (pintype "passive"))
      (node (ref "C9") (pin "2") (pinfunction "2_2") (pintype "passive"))
      (node (ref "D4") (pin "1") (pinfunction "A_1") (pintype "passive"))
      (node (ref "D5") (pin "1") (pinfunction "A_1") (pintype "passive"))
      (node (ref "D6") (pin "1") (pinfunction "A_1") (pintype "passive"))
      (node (ref "R7") (pin "2") (pinfunction "2_2") (pintype "passive"))
      (node (ref "U1") (pin "4") (pinfunction "VCC_4") (pintype "passive"))
    )
    (net (code "74") (name "unconnected-(S1-A2-Pad2)") (class "Default")
      (node (ref "S1") (pin "2") (pinfunction "A2_2") (pintype "passive"))
    )
    (net (code "75") (name "unconnected-(S1-B2-Pad3)") (class "Default")
      (node (ref "S1") (pin "3") (pinfunction "B2_3") (pintype "passive"))
    )
    (net (code "76") (name "unconnected-(U1-NC-Pad5)") (class "Default")
      (node (ref "U1") (pin "5") (pinfunction "NC_5") (pintype "passive+no_connect"))
    )
    (net (code "77") (name "unconnected-(U1-NC-Pad7)") (class "Default")
      (node (ref "U1") (pin "7") (pinfunction "NC_7") (pintype "passive+no_connect"))
    )
    (net (code "78") (name "unconnected-(U1-NC-Pad8)") (class "Default")
      (node (ref "U1") (pin "8") (pinfunction "NC_8") (pintype "passive+no_connect"))
    )
    (net (code "79") (name "unconnected-(U1-NC-Pad21)") (class "Default")
      (node (ref "U1") (pin "21") (pinfunction "NC_21") (pintype "passive+no_connect"))
    )
    (net (code "80") (name "unconnected-(U3-NC-Pad5)") (class "Default")
      (node (ref "U3") (pin "5") (pinfunction "NC_5") (pintype "passive"))
    )
    (net (code "81") (name "unconnected-(U3-NC-Pad8)") (class "Default")
      (node (ref "U3") (pin "8") (pinfunction "NC_8") (pintype "passive"))
    )
    (net (code "82") (name "unconnected-(U4A-PA5-Pad21)") (class "Default")
      (node (ref "U4") (pin "21") (pinfunction "PA5_21") (pintype "bidirectional+no_connect"))
    )
    (net (code "83") (name "unconnected-(U4A-PA6-Pad22)") (class "Default")
      (node (ref "U4") (pin "22") (pinfunction "PA6_22") (pintype "bidirectional+no_connect"))
    )
    (net (code "84") (name "unconnected-(U4A-PA7-Pad23)") (class "Default")
      (node (ref "U4") (pin "23") (pinfunction "PA7_23") (pintype "bidirectional+no_connect"))
    )
    (net (code "85") (name "unconnected-(U4A-PA15(JTDI)-Pad50)") (class "Default")
      (node (ref "U4") (pin "50") (pinfunction "PA15(JTDI)_50") (pintype "bidirectional+no_connect"))
    )
    (net (code "86") (name "unconnected-(U4A-PB10-Pad29)") (class "Default")
      (node (ref "U4") (pin "29") (pinfunction "PB10_29") (pintype "bidirectional+no_connect"))
    )
    (net (code "87") (name "unconnected-(U4A-PB11-Pad30)") (class "Default")
      (node (ref "U4") (pin "30") (pinfunction "PB11_30") (pintype "bidirectional+no_connect"))
    )
    (net (code "88") (name "unconnected-(U4A-PB12-Pad33)") (class "Default")
      (node (ref "U4") (pin "33") (pinfunction "PB12_33") (pintype "bidirectional+no_connect"))
    )
    (net (code "89") (name "unconnected-(U4A-PB14-Pad35)") (class "Default")
      (node (ref "U4") (pin "35") (pinfunction "PB14_35") (pintype "bidirectional+no_connect"))
    )
    (net (code "90") (name "unconnected-(U4A-PB15-Pad36)") (class "Default")
      (node (ref "U4") (pin "36") (pinfunction "PB15_36") (pintype "bidirectional+no_connect"))
    )
    (net (code "91") (name "unconnected-(U4A-PC0-Pad8)") (class "Default")
      (node (ref "U4") (pin "8") (pinfunction "PC0_8") (pintype "bidirectional+no_connect"))
    )
    (net (code "92") (name "unconnected-(U4A-PC1-Pad9)") (class "Default")
      (node (ref "U4") (pin "9") (pinfunction "PC1_9") (pintype "bidirectional+no_connect"))
    )
    (net (code "93") (name "unconnected-(U4A-PC2-Pad10)") (class "Default")
      (node (ref "U4") (pin "10") (pinfunction "PC2_10") (pintype "bidirectional+no_connect"))
    )
    (net (code "94") (name "unconnected-(U4A-PC3-Pad11)") (class "Default")
      (node (ref "U4") (pin "11") (pinfunction "PC3_11") (pintype "bidirectional+no_connect"))
    )
    (net (code "95") (name "unconnected-(U4A-PC6-Pad37)") (class "Default")
      (node (ref "U4") (pin "37") (pinfunction "PC6_37") (pintype "bidirectional+no_connect"))
    )
    (net (code "96") (name "unconnected-(U4A-PC7-Pad38)") (class "Default")
      (node (ref "U4") (pin "38") (pinfunction "PC7_38") (pintype "bidirectional+no_connect"))
    )
    (net (code "97") (name "unconnected-(U4A-PC8-Pad39)") (class "Default")
      (node (ref "U4") (pin "39") (pinfunction "PC8_39") (pintype "bidirectional+no_connect"))
    )
    (net (code "98") (name "unconnected-(U4A-PC9-Pad40)") (class "Default")
      (node (ref "U4") (pin "40") (pinfunction "PC9_40") (pintype "bidirectional+no_connect"))
    )
    (net (code "99") (name "unconnected-(U4A-PC10-Pad51)") (class "Default")
      (node (ref "U4") (pin "51") (pinfunction "PC10_51") (pintype "bidirectional+no_connect"))
    )
    (net (code "100") (name "unconnected-(U4A-PC11-Pad52)") (class "Default")
      (node (ref "U4") (pin "52") (pinfunction "PC11_52") (pintype "bidirectional+no_connect"))
    )
    (net (code "101") (name "unconnected-(U4A-PC12-Pad53)") (class "Default")
      (node (ref "U4") (pin "53") (pinfunction "PC12_53") (pintype "bidirectional+no_connect"))
    )
    (net (code "102") (name "unconnected-(U4A-PC15-OSC32_OUT(PC15)-Pad4)") (class "Default")
      (node (ref "U4") (pin "4") (pinfunction "PC15-OSC32_OUT(PC15)_4") (pintype "bidirectional+no_connect"))
    )
    (net (code "103") (name "unconnected-(U6-A-Pad7)") (class "Default")
      (node (ref "U6") (pin "7") (pinfunction "A_7") (pintype "passive"))
    )
    (net (code "104") (name "unconnected-(U6-B-Pad6)") (class "Default")
      (node (ref "U6") (pin "6") (pinfunction "B_6") (pintype "passive"))
    )
    (net (code "105") (name "unconnected-(U6-I{slash}PWM-Pad14)") (class "Default")
      (node (ref "U6") (pin "14") (pinfunction "I/PWM_14") (pintype "passive"))
    )
    (net (code "106") (name "unconnected-(U6-U-Pad10)") (class "Default")
      (node (ref "U6") (pin "10") (pinfunction "U_10") (pintype "passive"))
    )
    (net (code "107") (name "unconnected-(U6-V-Pad9)") (class "Default")
      (node (ref "U6") (pin "9") (pinfunction "V_9") (pintype "passive"))
    )
    (net (code "108") (name "unconnected-(U6-W{slash}PWM-Pad8)") (class "Default")
      (node (ref "U6") (pin "8") (pinfunction "W/PWM_8") (pintype "passive"))
    )
  )
)
